# Input_AFE.net
KiCad netlist of a schematic drawn in Altium Designer
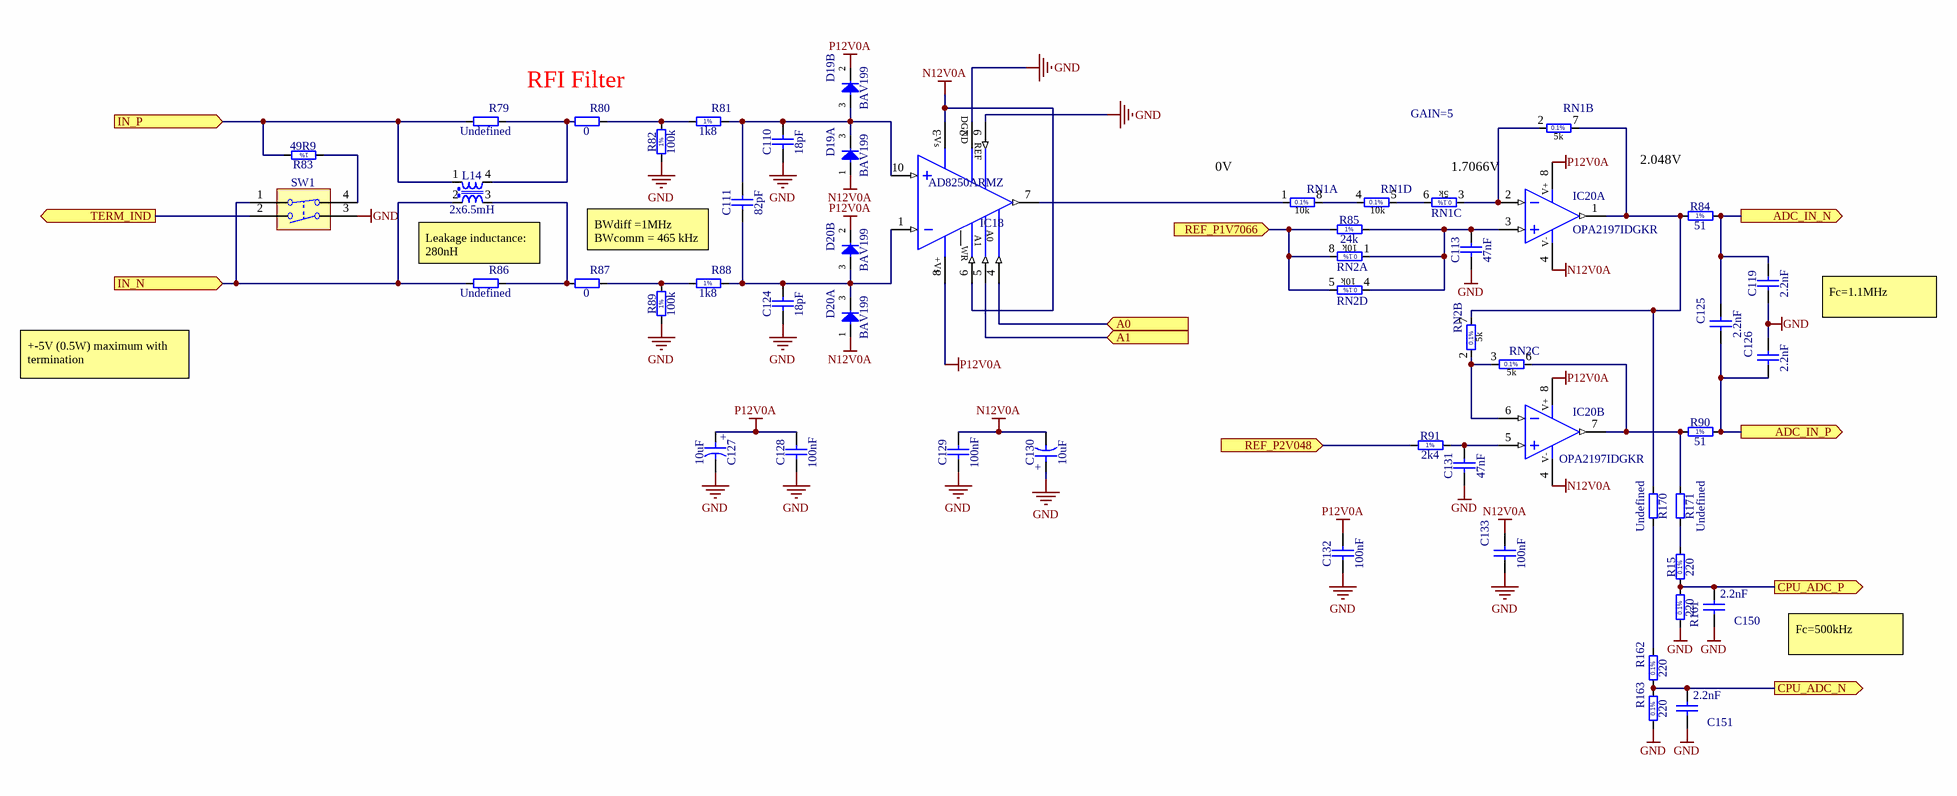
[diagram p0: Input_AFE.SchDoc]

(export (version "E")
  (design (tool "Eeschema 10.0.6"))
  (components
    (comp (ref "C110")
      (value "18pF")
      (footprint "CAPC1608X87N")
      (description "Non-polarised capacitor")
      (fields
        (field (name "PART NUMBER") "CC0603_18PF_50V_5%_NP0")
        (field (name "VOLTAGE") "50V")
        (field (name "AUTHOR") "CERN DEM JLC")
      )
      (libsource (lib "Capacitors") (part "Capacitor - non polarized"))
    )
    (comp (ref "C111")
      (value "82pF")
      (footprint "CAPC2012X90N")
      (description "Non-polarised capacitor")
      (fields
        (field (name "PART NUMBER") "CC0805_82PF_100V_1%_NP0_AVX_08051A820FAT2A")
        (field (name "VOLTAGE") "100V")
        (field (name "AUTHOR") "CERN DEM WB")
      )
      (libsource (lib "Capacitors") (part "Capacitor - non polarized"))
    )
    (comp (ref "C113")
      (value "47nF")
      (footprint "CAPC2012X135N")
      (description "Non-polarised capacitor")
      (fields
        (field (name "PART NUMBER") "CC0805_47NF_25V_5%_C0G")
        (field (name "VOLTAGE") "25V")
        (field (name "AUTHOR") "CERN DEM JLC")
      )
      (libsource (lib "Capacitors") (part "Capacitor - non polarized"))
    )
    (comp (ref "C119")
      (value "2.2nF")
      (footprint "CAPC2013X100N")
      (description "Non-polarised capacitor")
      (fields
        (field (name "PART NUMBER") "CC0805_2.2NF_25V_1%_C0G")
        (field (name "VOLTAGE") "25V")
        (field (name "AUTHOR") "CERN DEM JLC")
      )
      (libsource (lib "Capacitors") (part "Capacitor - non polarized"))
    )
    (comp (ref "C124")
      (value "18pF")
      (footprint "CAPC1608X87N")
      (description "Non-polarised capacitor")
      (fields
        (field (name "PART NUMBER") "CC0603_18PF_50V_5%_NP0")
        (field (name "VOLTAGE") "50V")
        (field (name "AUTHOR") "CERN DEM JLC")
      )
      (libsource (lib "Capacitors") (part "Capacitor - non polarized"))
    )
    (comp (ref "C125")
      (value "2.2nF")
      (footprint "CAPC2013X100N")
      (description "Non-polarised capacitor")
      (fields
        (field (name "PART NUMBER") "CC0805_2.2NF_25V_1%_C0G")
        (field (name "VOLTAGE") "25V")
        (field (name "AUTHOR") "CERN DEM JLC")
      )
      (libsource (lib "Capacitors") (part "Capacitor - non polarized"))
    )
    (comp (ref "C126")
      (value "2.2nF")
      (footprint "CAPC2013X100N")
      (description "Non-polarised capacitor")
      (fields
        (field (name "PART NUMBER") "CC0805_2.2NF_25V_1%_C0G")
        (field (name "VOLTAGE") "25V")
        (field (name "AUTHOR") "CERN DEM JLC")
      )
      (libsource (lib "Capacitors") (part "Capacitor - non polarized"))
    )
    (comp (ref "C127")
      (value "10uF")
      (footprint "CAPMP3216X180N")
      (description "Polarised capacitor")
      (fields
        (field (name "PART NUMBER") "CTE3216-18_10UF_16V_20%_AVX_TCJ")
        (field (name "VOLTAGE") "16V")
        (field (name "AUTHOR") "CERN DEM JLC")
      )
      (libsource (lib "Capacitors") (part "Capacitor - polarized"))
    )
    (comp (ref "C128")
      (value "100nF")
      (footprint "CAPC1005X55N")
      (description "Non-polarised capacitor")
      (fields
        (field (name "PART NUMBER") "CC0402_100NF_16V_10%_X7R")
        (field (name "VOLTAGE") "16V")
        (field (name "AUTHOR") "CERN DEM JLC")
      )
      (libsource (lib "Capacitors") (part "Capacitor - non polarized"))
    )
    (comp (ref "C129")
      (value "100nF")
      (footprint "CAPC1005X55N")
      (description "Non-polarised capacitor")
      (fields
        (field (name "PART NUMBER") "CC0402_100NF_16V_10%_X7R")
        (field (name "VOLTAGE") "16V")
        (field (name "AUTHOR") "CERN DEM JLC")
      )
      (libsource (lib "Capacitors") (part "Capacitor - non polarized"))
    )
    (comp (ref "C130")
      (value "10uF")
      (footprint "CAPMP3216X180N")
      (description "Polarised capacitor")
      (fields
        (field (name "PART NUMBER") "CTE3216-18_10UF_16V_20%_AVX_TCJ")
        (field (name "VOLTAGE") "16V")
        (field (name "AUTHOR") "CERN DEM JLC")
      )
      (libsource (lib "Capacitors") (part "Capacitor - polarized"))
    )
    (comp (ref "C131")
      (value "47nF")
      (footprint "CAPC2012X135N")
      (description "Non-polarised capacitor")
      (fields
        (field (name "PART NUMBER") "CC0805_47NF_25V_5%_C0G")
        (field (name "VOLTAGE") "25V")
        (field (name "AUTHOR") "CERN DEM JLC")
      )
      (libsource (lib "Capacitors") (part "Capacitor - non polarized"))
    )
    (comp (ref "C132")
      (value "100nF")
      (footprint "CAPC1005X55N")
      (description "Non-polarised capacitor")
      (fields
        (field (name "PART NUMBER") "CC0402_100NF_16V_10%_X7R")
        (field (name "VOLTAGE") "16V")
        (field (name "AUTHOR") "CERN DEM JLC")
      )
      (libsource (lib "Capacitors") (part "Capacitor - non polarized"))
    )
    (comp (ref "C133")
      (value "100nF")
      (footprint "CAPC1005X55N")
      (description "Non-polarised capacitor")
      (fields
        (field (name "PART NUMBER") "CC0402_100NF_16V_10%_X7R")
        (field (name "VOLTAGE") "16V")
        (field (name "AUTHOR") "CERN DEM JLC")
      )
      (libsource (lib "Capacitors") (part "Capacitor - non polarized"))
    )
    (comp (ref "C150")
      (value "2.2nF")
      (footprint "CAPC2013X100N")
      (description "Non-polarised capacitor")
      (fields
        (field (name "PART NUMBER") "CC0805_2.2NF_25V_1%_C0G")
        (field (name "VOLTAGE") "25V")
        (field (name "AUTHOR") "CERN DEM JLC")
      )
      (libsource (lib "Capacitors") (part "Capacitor - non polarized"))
    )
    (comp (ref "C151")
      (value "2.2nF")
      (footprint "CAPC2013X100N")
      (description "Non-polarised capacitor")
      (fields
        (field (name "PART NUMBER") "CC0805_2.2NF_25V_1%_C0G")
        (field (name "VOLTAGE") "25V")
        (field (name "AUTHOR") "CERN DEM JLC")
      )
      (libsource (lib "Capacitors") (part "Capacitor - non polarized"))
    )
    (comp (ref "D19")
      (value "BAV199")
      (footprint "SOT95P240X110-3N")
      (description "Serial Diode")
      (fields
        (field (name "VOLTAGE") "75V")
        (field (name "POWER") "250mW")
        (field (name "AUTHOR") "CERN DEM JMW")
      )
      (libsource (lib "ICs And Semiconductors") (part "Diode x2 A1C3_A3C2"))
    )
    (comp (ref "D20")
      (value "BAV199")
      (footprint "SOT95P240X110-3N")
      (description "Serial Diode")
      (fields
        (field (name "VOLTAGE") "75V")
        (field (name "POWER") "250mW")
        (field (name "AUTHOR") "CERN DEM JMW")
      )
      (libsource (lib "ICs And Semiconductors") (part "Diode x2 A1C3_A3C2"))
    )
    (comp (ref "IC18")
      (value "AD8250ARMZ")
      (footprint "SOP50P490X110-10N")
      (description "10MHz, 20V/us, G= 1, 2, 5, 10 iCMOS Programmable Gain Instrumentation Amplifier")
      (fields (field (name "MANUFACTURER") "ANALOG DEVICES") (field (name "AUTHOR") "CERN DEM JLC"))
      (libsource (lib "ICs And Semiconductors") (part "AD8250"))
    )
    (comp (ref "IC20")
      (value "OPA2197IDGKR")
      (footprint "SOP65P490X110-8N")
      (description "36-V, Precision, Rail-to-Rail Input Output, Low Offset Voltage Op Amp 8-VSSOP")
      (fields (field (name "MANUFACTURER") "TEXAS INSTRUMENTS") (field (name "AUTHOR") "GK"))
      (libsource (lib "LIBRARY_SCH") (part "OA_OPA2197IDGKR"))
    )
    (comp (ref "L14")
      (value "2x6.5mH")
      (footprint "IND_WURTH_WE-SL2")
      (description "Inductor Common Mode")
      (fields
        (field (name "PART NUMBER") "IND_6.5MH_50%_WURTH_WE-SL2-744229")
        (field (name "POWER") "400mA")
        (field (name "AUTHOR") "CERN DEM JLC")
      )
      (libsource (lib "Inductors & Transformers") (part "Inductor Common Mode 1Dot-4 2Dot-3"))
    )
    (comp (ref "R15")
      (value "220")
      (footprint "RESC1608X64N")
      (description "Resistor - 0.1%")
      (fields
        (field (name "PART NUMBER") "R0603_220R_0.1%_0.1W_25PPM")
        (field (name "POWER") "0.1W")
        (field (name "AUTHOR") "CERN DEM JLC")
      )
      (libsource (lib "Resistors") (part "Resistor - 0.1%"))
    )
    (comp (ref "R79")
      (value "Undefined")
      (footprint "RESC1608X55N")
      (description "Resistor")
      (fields (field (name "PART NUMBER") "R0603_NO-VALUE") (field (name "AUTHOR") "CERN DEM JLC"))
      (libsource (lib "Resistors") (part "Resistor"))
    )
    (comp (ref "R80")
      (value "0")
      (footprint "RESC1608X55N")
      (description "Resistor")
      (fields
        (field (name "PART NUMBER") "R0603_0R_JUMPER")
        (field (name "MANUFACTURER") "GENERIC")
        (field (name "AUTHOR") "CERN DEM JLC")
      )
      (libsource (lib "Resistors") (part "Resistor"))
    )
    (comp (ref "R81")
      (value "1k8")
      (footprint "RESC1608X55N")
      (description "Resistor - 1%")
      (fields
        (field (name "PART NUMBER") "R0603_1K8_1%_0.1W_100PPM")
        (field (name "POWER") "0.1W")
        (field (name "AUTHOR") "CERN DEM JLC")
      )
      (libsource (lib "Resistors") (part "Resistor - 1%"))
    )
    (comp (ref "R82")
      (value "100k")
      (footprint "RESC1608X55N")
      (description "Resistor - 1%")
      (fields
        (field (name "PART NUMBER") "R0603_100K_1%_0.1W_100PPM")
        (field (name "POWER") "0.1W")
        (field (name "AUTHOR") "CERN DEM JLC")
      )
      (libsource (lib "Resistors") (part "Resistor - 1%"))
    )
    (comp (ref "R83")
      (value "49R9")
      (footprint "RESC6331X70N")
      (description "Resistor - 1%")
      (fields
        (field (name "PART NUMBER") "R2512_49R9_1%_1W_100PPM_VISHAY_CRCW")
        (field (name "POWER") "1W")
        (field (name "AUTHOR") "CERN DEM JLC")
      )
      (libsource (lib "Resistors") (part "Resistor - 1%"))
    )
    (comp (ref "R84")
      (value "51")
      (footprint "RESC1005X40N")
      (description "Resistor - 1%")
      (fields
        (field (name "PART NUMBER") "R0402_51R_1%_0.0625W_100PPM")
        (field (name "POWER") "0.0625W")
        (field (name "AUTHOR") "CERN DEM JLC")
      )
      (libsource (lib "Resistors") (part "Resistor - 1%"))
    )
    (comp (ref "R85")
      (value "24k")
      (footprint "RESC1608X55N")
      (description "Resistor - 1%")
      (fields
        (field (name "PART NUMBER") "R0603_24K_1%_0.1W_100PPM")
        (field (name "POWER") "0.1W")
        (field (name "AUTHOR") "CERN DEM JLC")
      )
      (libsource (lib "Resistors") (part "Resistor - 1%"))
    )
    (comp (ref "R86")
      (value "Undefined")
      (footprint "RESC1608X55N")
      (description "Resistor")
      (fields (field (name "PART NUMBER") "R0603_NO-VALUE") (field (name "AUTHOR") "CERN DEM JLC"))
      (libsource (lib "Resistors") (part "Resistor"))
    )
    (comp (ref "R87")
      (value "0")
      (footprint "RESC1608X55N")
      (description "Resistor")
      (fields
        (field (name "PART NUMBER") "R0603_0R_JUMPER")
        (field (name "MANUFACTURER") "GENERIC")
        (field (name "AUTHOR") "CERN DEM JLC")
      )
      (libsource (lib "Resistors") (part "Resistor"))
    )
    (comp (ref "R88")
      (value "1k8")
      (footprint "RESC1608X55N")
      (description "Resistor - 1%")
      (fields
        (field (name "PART NUMBER") "R0603_1K8_1%_0.1W_100PPM")
        (field (name "POWER") "0.1W")
        (field (name "AUTHOR") "CERN DEM JLC")
      )
      (libsource (lib "Resistors") (part "Resistor - 1%"))
    )
    (comp (ref "R89")
      (value "100k")
      (footprint "RESC1608X55N")
      (description "Resistor - 1%")
      (fields
        (field (name "PART NUMBER") "R0603_100K_1%_0.1W_100PPM")
        (field (name "POWER") "0.1W")
        (field (name "AUTHOR") "CERN DEM JLC")
      )
      (libsource (lib "Resistors") (part "Resistor - 1%"))
    )
    (comp (ref "R90")
      (value "51")
      (footprint "RESC1005X40N")
      (description "Resistor - 1%")
      (fields
        (field (name "PART NUMBER") "R0402_51R_1%_0.0625W_100PPM")
        (field (name "POWER") "0.0625W")
        (field (name "AUTHOR") "CERN DEM JLC")
      )
      (libsource (lib "Resistors") (part "Resistor - 1%"))
    )
    (comp (ref "R91")
      (value "2k4")
      (footprint "RESC1005X40N")
      (description "Resistor - 1%")
      (fields
        (field (name "PART NUMBER") "R0402_2K4_1%_0.0625W_100PPM")
        (field (name "POWER") "0.0625W")
        (field (name "AUTHOR") "CERN DEM JLC")
      )
      (libsource (lib "Resistors") (part "Resistor - 1%"))
    )
    (comp (ref "R161")
      (value "220")
      (footprint "RESC1608X64N")
      (description "Resistor - 0.1%")
      (fields
        (field (name "PART NUMBER") "R0603_220R_0.1%_0.1W_25PPM")
        (field (name "POWER") "0.1W")
        (field (name "AUTHOR") "CERN DEM JLC")
      )
      (libsource (lib "Resistors") (part "Resistor - 0.1%"))
    )
    (comp (ref "R162")
      (value "220")
      (footprint "RESC1608X64N")
      (description "Resistor - 0.1%")
      (fields
        (field (name "PART NUMBER") "R0603_220R_0.1%_0.1W_25PPM")
        (field (name "POWER") "0.1W")
        (field (name "AUTHOR") "CERN DEM JLC")
      )
      (libsource (lib "Resistors") (part "Resistor - 0.1%"))
    )
    (comp (ref "R163")
      (value "220")
      (footprint "RESC1608X64N")
      (description "Resistor - 0.1%")
      (fields
        (field (name "PART NUMBER") "R0603_220R_0.1%_0.1W_25PPM")
        (field (name "POWER") "0.1W")
        (field (name "AUTHOR") "CERN DEM JLC")
      )
      (libsource (lib "Resistors") (part "Resistor - 0.1%"))
    )
    (comp (ref "R170")
      (value "Undefined")
      (footprint "RESC1608X55N")
      (description "Resistor")
      (fields (field (name "PART NUMBER") "R0603_NO-VALUE") (field (name "AUTHOR") "CERN DEM JLC"))
      (libsource (lib "Resistors") (part "Resistor"))
    )
    (comp (ref "R171")
      (value "Undefined")
      (footprint "RESC1608X55N")
      (description "Resistor")
      (fields (field (name "PART NUMBER") "R0603_NO-VALUE") (field (name "AUTHOR") "CERN DEM JLC"))
      (libsource (lib "Resistors") (part "Resistor"))
    )
    (comp (ref "RN1")
      (value "10k 5K 5K 10K")
      (footprint "SOIC127P600X175-8N")
      (description "DIL8 Resistor Network 4 Resistors 10k-5k-5k-10k 0.1%")
      (fields
        (field (name "PART NUMBER") "RN_10K_5K_VISHAY_AORN2-1AT3")
        (field (name "POWER") "4x0.1W")
        (field (name "AUTHOR") "CERN DEM JLC")
      )
      (libsource (lib "Resistors") (part "RN DIL8_4xR_10k-5k-5k-10k_0.1%"))
    )
    (comp (ref "RN2")
      (value "10k 5K 5K 10K")
      (footprint "SOIC127P600X175-8N")
      (description "DIL8 Resistor Network 4 Resistors 10k-5k-5k-10k 0.1%")
      (fields
        (field (name "PART NUMBER") "RN_10K_5K_VISHAY_AORN2-1AT3")
        (field (name "POWER") "4x0.1W")
        (field (name "AUTHOR") "CERN DEM JLC")
      )
      (libsource (lib "Resistors") (part "RN DIL8_4xR_10k-5k-5k-10k_0.1%"))
    )
    (comp (ref "SW1")
      (value "Switch")
      (footprint "SW_CTS_204-121ST")
      (description "2x SPST DIP Switch 1NO + 1NF")
      (fields
        (field (name "PART NUMBER") "SW_CTS_204-121ST")
        (field (name "MANUFACTURER") "CTS")
        (field (name "AUTHOR") "CERN DEM JLC")
      )
      (libsource (lib "Eletro-mechanical") (part "SW_CTS_204-121ST"))
    )
  )
  (nets
    (net (code "1") (name "/A0") (class "Default")
      (node (ref "IC18") (pin "4") (pinfunction "A0_4") (pintype "input"))
    )
    (net (code "2") (name "/A1") (class "Default")
      (node (ref "IC18") (pin "5") (pinfunction "A1_5") (pintype "input"))
    )
    (net (code "3") (name "/ADC_IN_N") (class "Default")
      (node (ref "C119") (pin "2") (pinfunction "2_2") (pintype "passive"))
      (node (ref "C125") (pin "2") (pinfunction "2_2") (pintype "passive"))
      (node (ref "R84") (pin "2") (pinfunction "2_2") (pintype "passive"))
    )
    (net (code "4") (name "/ADC_IN_P") (class "Default")
      (node (ref "C125") (pin "1") (pinfunction "1_1") (pintype "passive"))
      (node (ref "C126") (pin "1") (pinfunction "1_1") (pintype "passive"))
      (node (ref "R90") (pin "2") (pinfunction "2_2") (pintype "passive"))
    )
    (net (code "5") (name "/CPU_ADC_N") (class "Default")
      (node (ref "C151") (pin "2") (pinfunction "2_2") (pintype "passive"))
      (node (ref "R162") (pin "1") (pinfunction "1_1") (pintype "passive"))
      (node (ref "R163") (pin "2") (pinfunction "2_2") (pintype "passive"))
    )
    (net (code "6") (name "/CPU_ADC_P") (class "Default")
      (node (ref "C150") (pin "2") (pinfunction "2_2") (pintype "passive"))
      (node (ref "R15") (pin "1") (pinfunction "1_1") (pintype "passive"))
      (node (ref "R161") (pin "2") (pinfunction "2_2") (pintype "passive"))
    )
    (net (code "7") (name "/IN_N") (class "Default")
      (node (ref "L14") (pin "2") (pinfunction "2_2") (pintype "passive"))
      (node (ref "R86") (pin "1") (pinfunction "1_1") (pintype "passive"))
      (node (ref "SW1") (pin "1") (pinfunction "1_1") (pintype "passive"))
    )
    (net (code "8") (name "/IN_P") (class "Default")
      (node (ref "L14") (pin "1") (pinfunction "1_1") (pintype "passive"))
      (node (ref "R79") (pin "1") (pinfunction "1_1") (pintype "passive"))
      (node (ref "R83") (pin "2") (pinfunction "2_2") (pintype "passive"))
    )
    (net (code "9") (name "/REF_P1V7066") (class "Default")
      (node (ref "R85") (pin "1") (pinfunction "1_1") (pintype "passive"))
      (node (ref "RN2") (pin "5") (pinfunction "5_5") (pintype "passive"))
      (node (ref "RN2") (pin "8") (pinfunction "8_8") (pintype "passive"))
    )
    (net (code "10") (name "/REF_P2V048") (class "Default")
      (node (ref "R91") (pin "1") (pinfunction "1_1") (pintype "passive"))
    )
    (net (code "11") (name "/TERM_IND") (class "Default")
      (node (ref "SW1") (pin "2") (pinfunction "2_2") (pintype "passive"))
    )
    (net (code "12") (name "GND") (class "Default")
      (node (ref "C110") (pin "1") (pinfunction "1_1") (pintype "passive"))
      (node (ref "C113") (pin "1") (pinfunction "1_1") (pintype "passive"))
      (node (ref "C119") (pin "1") (pinfunction "1_1") (pintype "passive"))
      (node (ref "C124") (pin "1") (pinfunction "1_1") (pintype "passive"))
      (node (ref "C126") (pin "2") (pinfunction "2_2") (pintype "passive"))
      (node (ref "C127") (pin "2") (pinfunction "2_2") (pintype "passive"))
      (node (ref "C128") (pin "1") (pinfunction "1_1") (pintype "passive"))
      (node (ref "C129") (pin "1") (pinfunction "1_1") (pintype "passive"))
      (node (ref "C130") (pin "1") (pinfunction "1_1") (pintype "passive"))
      (node (ref "C131") (pin "1") (pinfunction "1_1") (pintype "passive"))
      (node (ref "C132") (pin "1") (pinfunction "1_1") (pintype "passive"))
      (node (ref "C133") (pin "1") (pinfunction "1_1") (pintype "passive"))
      (node (ref "C150") (pin "1") (pinfunction "1_1") (pintype "passive"))
      (node (ref "C151") (pin "1") (pinfunction "1_1") (pintype "passive"))
      (node (ref "IC18") (pin "2") (pinfunction "DGND_2") (pintype "power_in"))
      (node (ref "IC18") (pin "9") (pinfunction "REF_9") (pintype "input"))
      (node (ref "R161") (pin "1") (pinfunction "1_1") (pintype "passive"))
      (node (ref "R163") (pin "1") (pinfunction "1_1") (pintype "passive"))
      (node (ref "R82") (pin "1") (pinfunction "1_1") (pintype "passive"))
      (node (ref "R89") (pin "1") (pinfunction "1_1") (pintype "passive"))
      (node (ref "SW1") (pin "3") (pinfunction "3_3") (pintype "passive"))
    )
    (net (code "13") (name "N12V0A") (class "Default")
      (node (ref "C129") (pin "2") (pinfunction "2_2") (pintype "passive"))
      (node (ref "C130") (pin "2") (pinfunction "2_2") (pintype "passive"))
      (node (ref "C133") (pin "2") (pinfunction "2_2") (pintype "passive"))
      (node (ref "D19") (pin "1") (pinfunction "A_1") (pintype "passive"))
      (node (ref "D20") (pin "1") (pinfunction "A_1") (pintype "passive"))
      (node (ref "IC18") (pin "3") (pinfunction "-VS_3") (pintype "power_in"))
      (node (ref "IC18") (pin "6") (pinfunction "~{WR}_6") (pintype "input"))
      (node (ref "IC20") (pin "4") (pinfunction "V-_4") (pintype "power_in"))
    )
    (net (code "14") (name "Net-(D19A-COMAC)") (class "Default")
      (node (ref "C110") (pin "2") (pinfunction "2_2") (pintype "passive"))
      (node (ref "C111") (pin "2") (pinfunction "2_2") (pintype "passive"))
      (node (ref "D19") (pin "3") (pinfunction "COMAC_3") (pintype "passive"))
      (node (ref "IC18") (pin "10") (pinfunction "+IN_10") (pintype "input"))
      (node (ref "R81") (pin "2") (pinfunction "2_2") (pintype "passive"))
    )
    (net (code "15") (name "Net-(D20A-COMAC)") (class "Default")
      (node (ref "C111") (pin "1") (pinfunction "1_1") (pintype "passive"))
      (node (ref "C124") (pin "2") (pinfunction "2_2") (pintype "passive"))
      (node (ref "D20") (pin "3") (pinfunction "COMAC_3") (pintype "passive"))
      (node (ref "IC18") (pin "1") (pinfunction "-IN_1") (pintype "input"))
      (node (ref "R88") (pin "2") (pinfunction "2_2") (pintype "passive"))
    )
    (net (code "16") (name "Net-(IC18-OUT)") (class "Default")
      (node (ref "IC18") (pin "7") (pinfunction "OUT_7") (pintype "output"))
      (node (ref "RN1") (pin "1") (pinfunction "1_1") (pintype "passive"))
    )
    (net (code "17") (name "Net-(IC20A-IN+)") (class "Default")
      (node (ref "C113") (pin "2") (pinfunction "2_2") (pintype "passive"))
      (node (ref "IC20") (pin "3") (pinfunction "IN+_3") (pintype "input"))
      (node (ref "R85") (pin "2") (pinfunction "2_2") (pintype "passive"))
      (node (ref "RN2") (pin "1") (pinfunction "1_1") (pintype "passive"))
      (node (ref "RN2") (pin "4") (pinfunction "4_4") (pintype "passive"))
    )
    (net (code "18") (name "Net-(IC20A-IN-)") (class "Default")
      (node (ref "IC20") (pin "2") (pinfunction "IN-_2") (pintype "input"))
      (node (ref "RN1") (pin "2") (pinfunction "2_2") (pintype "passive"))
      (node (ref "RN1") (pin "3") (pinfunction "3_3") (pintype "passive"))
    )
    (net (code "19") (name "Net-(IC20A-OUT)") (class "Default")
      (node (ref "IC20") (pin "1") (pinfunction "OUT_1") (pintype "output"))
      (node (ref "R170") (pin "1") (pinfunction "1_1") (pintype "passive"))
      (node (ref "R84") (pin "1") (pinfunction "1_1") (pintype "passive"))
      (node (ref "RN1") (pin "7") (pinfunction "7_7") (pintype "passive"))
      (node (ref "RN2") (pin "7") (pinfunction "7_7") (pintype "passive"))
    )
    (net (code "20") (name "Net-(IC20B-IN+)") (class "Default")
      (node (ref "C131") (pin "2") (pinfunction "2_2") (pintype "passive"))
      (node (ref "IC20") (pin "5") (pinfunction "IN+_5") (pintype "input"))
      (node (ref "R91") (pin "2") (pinfunction "2_2") (pintype "passive"))
    )
    (net (code "21") (name "Net-(IC20B-IN-)") (class "Default")
      (node (ref "IC20") (pin "6") (pinfunction "IN-_6") (pintype "input"))
      (node (ref "RN2") (pin "2") (pinfunction "2_2") (pintype "passive"))
      (node (ref "RN2") (pin "3") (pinfunction "3_3") (pintype "passive"))
    )
    (net (code "22") (name "Net-(IC20B-OUT)") (class "Default")
      (node (ref "IC20") (pin "7") (pinfunction "OUT_7") (pintype "output"))
      (node (ref "R171") (pin "1") (pinfunction "1_1") (pintype "passive"))
      (node (ref "R90") (pin "1") (pinfunction "1_1") (pintype "passive"))
      (node (ref "RN2") (pin "6") (pinfunction "6_6") (pintype "passive"))
    )
    (net (code "23") (name "Net-(L14-Pad3)") (class "Default")
      (node (ref "L14") (pin "3") (pinfunction "3_3") (pintype "passive"))
      (node (ref "R86") (pin "2") (pinfunction "2_2") (pintype "passive"))
      (node (ref "R87") (pin "1") (pinfunction "1_1") (pintype "passive"))
    )
    (net (code "24") (name "Net-(L14-Pad4)") (class "Default")
      (node (ref "L14") (pin "4") (pinfunction "4_4") (pintype "passive"))
      (node (ref "R79") (pin "2") (pinfunction "2_2") (pintype "passive"))
      (node (ref "R80") (pin "1") (pinfunction "1_1") (pintype "passive"))
    )
    (net (code "25") (name "Net-(R15-Pad2)") (class "Default")
      (node (ref "R15") (pin "2") (pinfunction "2_2") (pintype "passive"))
      (node (ref "R171") (pin "2") (pinfunction "2_2") (pintype "passive"))
    )
    (net (code "26") (name "Net-(R80-Pad2)") (class "Default")
      (node (ref "R80") (pin "2") (pinfunction "2_2") (pintype "passive"))
      (node (ref "R81") (pin "1") (pinfunction "1_1") (pintype "passive"))
      (node (ref "R82") (pin "2") (pinfunction "2_2") (pintype "passive"))
    )
    (net (code "27") (name "Net-(R83-Pad1)") (class "Default")
      (node (ref "R83") (pin "1") (pinfunction "1_1") (pintype "passive"))
      (node (ref "SW1") (pin "4") (pinfunction "4_4") (pintype "passive"))
    )
    (net (code "28") (name "Net-(R87-Pad2)") (class "Default")
      (node (ref "R87") (pin "2") (pinfunction "2_2") (pintype "passive"))
      (node (ref "R88") (pin "1") (pinfunction "1_1") (pintype "passive"))
      (node (ref "R89") (pin "2") (pinfunction "2_2") (pintype "passive"))
    )
    (net (code "29") (name "Net-(R162-Pad2)") (class "Default")
      (node (ref "R162") (pin "2") (pinfunction "2_2") (pintype "passive"))
      (node (ref "R170") (pin "2") (pinfunction "2_2") (pintype "passive"))
    )
    (net (code "30") (name "Net-(RN1-Pad4)") (class "Default")
      (node (ref "RN1") (pin "4") (pinfunction "4_4") (pintype "passive"))
      (node (ref "RN1") (pin "8") (pinfunction "8_8") (pintype "passive"))
    )
    (net (code "31") (name "Net-(RN1-Pad5)") (class "Default")
      (node (ref "RN1") (pin "5") (pinfunction "5_5") (pintype "passive"))
      (node (ref "RN1") (pin "6") (pinfunction "6_6") (pintype "passive"))
    )
    (net (code "32") (name "P12V0A") (class "Default")
      (node (ref "C127") (pin "1") (pinfunction "1_1") (pintype "passive"))
      (node (ref "C128") (pin "2") (pinfunction "2_2") (pintype "passive"))
      (node (ref "C132") (pin "2") (pinfunction "2_2") (pintype "passive"))
      (node (ref "D19") (pin "2") (pinfunction "C_2") (pintype "passive"))
      (node (ref "D20") (pin "2") (pinfunction "C_2") (pintype "passive"))
      (node (ref "IC18") (pin "8") (pinfunction "+VS_8") (pintype "power_in"))
      (node (ref "IC20") (pin "8") (pinfunction "V+_8") (pintype "power_in"))
    )
  )
)
